# Dise_o_de_FISICA_v16.net
KiCad netlist of a schematic drawn in EAGLE
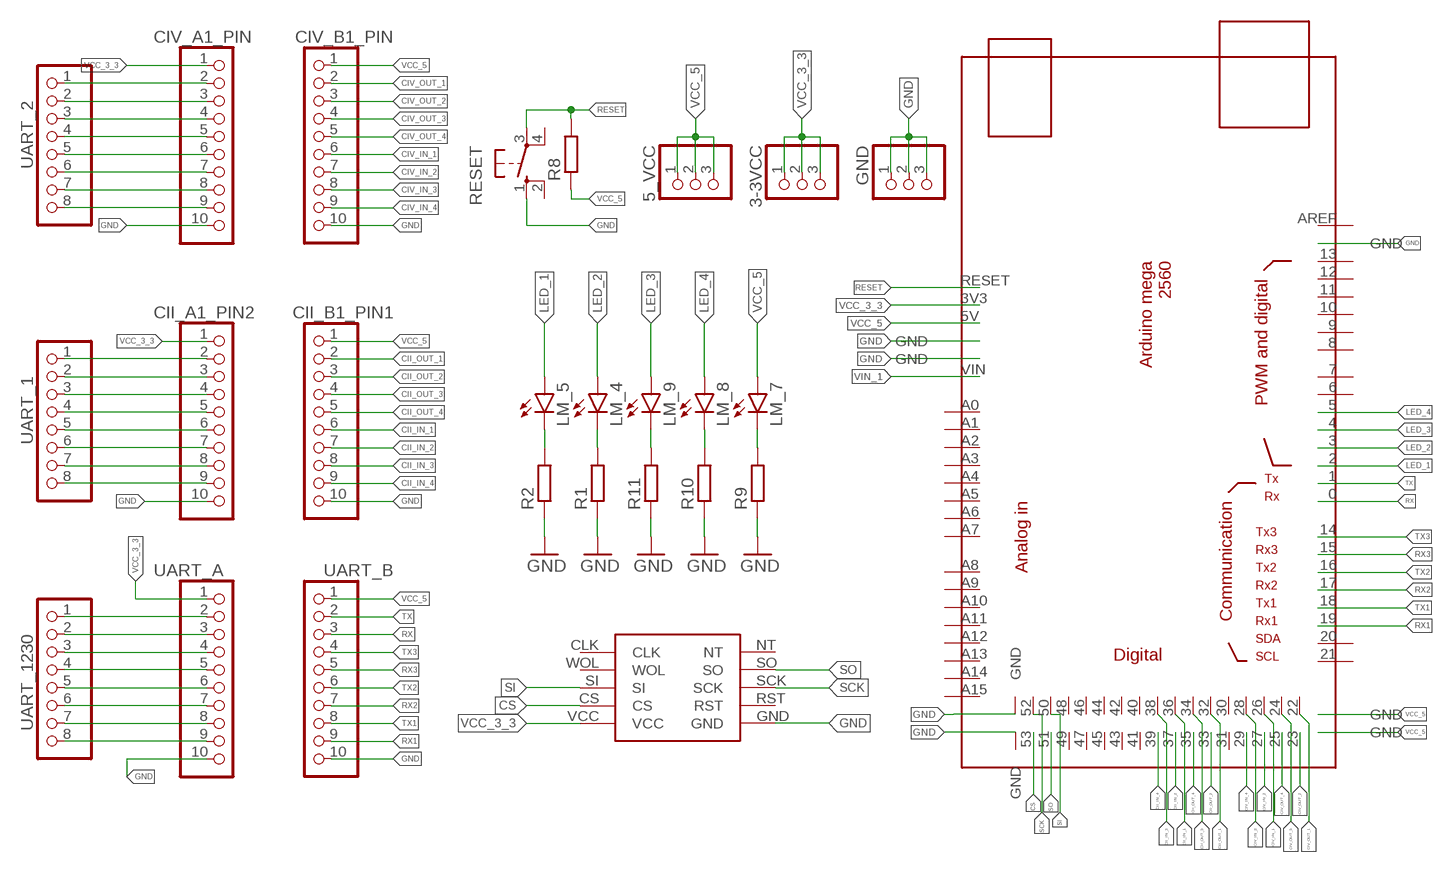
[diagram p0: schematic, sheet 1]

(export (version "E")
  (design (tool "Eeschema 10.0.6"))
  (components
    (comp (ref "3-3VCC")
      (value "PINHD-1X3")
      (footprint "eagle-import:1X03")
      (libsource (lib "eagle-import") (part "PINHD-1X3"))
    )
    (comp (ref "5_VCC")
      (value "PINHD-1X3")
      (footprint "eagle-import:1X03")
      (libsource (lib "eagle-import") (part "PINHD-1X3"))
    )
    (comp (ref "ARDUINOMEGA2560")
      (value "MEGA_DEVICE")
      (footprint "eagle-import:MEGAOUTLINE")
      (libsource (lib "eagle-import") (part "MEGA_DEVICE"))
    )
    (comp (ref "CII_A1_PIN2")
      (value "PINHD-1X10")
      (footprint "eagle-import:1X10-BIG")
      (libsource (lib "eagle-import") (part "PINHD-1X10"))
    )
    (comp (ref "CII_B1_PIN1")
      (value "PINHD-1X10")
      (footprint "eagle-import:1X10-BIG")
      (libsource (lib "eagle-import") (part "PINHD-1X10"))
    )
    (comp (ref "CIV_A1_PIN")
      (value "PINHD-1X10")
      (footprint "eagle-import:1X10-BIG")
      (libsource (lib "eagle-import") (part "PINHD-1X10"))
    )
    (comp (ref "CIV_B1_PIN")
      (value "PINHD-1X10")
      (footprint "eagle-import:1X10-BIG")
      (libsource (lib "eagle-import") (part "PINHD-1X10"))
    )
    (comp (ref "GND")
      (value "PINHD-1X3")
      (footprint "eagle-import:1X03")
      (libsource (lib "eagle-import") (part "PINHD-1X3"))
    )
    (comp (ref "LM_4")
      (value "LED3MM")
      (footprint "eagle-import:LED3MM")
      (libsource (lib "eagle-import") (part "LED3MM"))
    )
    (comp (ref "LM_5")
      (value "LED3MM")
      (footprint "eagle-import:LED3MM")
      (libsource (lib "eagle-import") (part "LED3MM"))
    )
    (comp (ref "LM_7")
      (value "LED3MM")
      (footprint "eagle-import:LED3MM")
      (libsource (lib "eagle-import") (part "LED3MM"))
    )
    (comp (ref "LM_8")
      (value "LED3MM")
      (footprint "eagle-import:LED3MM")
      (libsource (lib "eagle-import") (part "LED3MM"))
    )
    (comp (ref "LM_9")
      (value "LED3MM")
      (footprint "eagle-import:LED3MM")
      (libsource (lib "eagle-import") (part "LED3MM"))
    )
    (comp (ref "MODULO_ETHERNET")
      (value "ENC28J60")
      (footprint "eagle-import:ENC28J60")
      (libsource (lib "eagle-import") (part "ENC28J60"))
    )
    (comp (ref "R1")
      (value "R_CHIP-0805(2012-METRIC)")
      (footprint "eagle-import:RESC2012X65")
      (libsource (lib "eagle-import") (part "RCHIP-0805(2012-METRIC)_"))
    )
    (comp (ref "R2")
      (value "R_CHIP-0805(2012-METRIC)")
      (footprint "eagle-import:RESC2012X65")
      (libsource (lib "eagle-import") (part "RCHIP-0805(2012-METRIC)_"))
    )
    (comp (ref "R8")
      (value "R_CHIP-0805(2012-METRIC)")
      (footprint "eagle-import:RESC2012X65")
      (libsource (lib "eagle-import") (part "RCHIP-0805(2012-METRIC)_"))
    )
    (comp (ref "R9")
      (value "R_CHIP-0805(2012-METRIC)")
      (footprint "eagle-import:RESC2012X65")
      (libsource (lib "eagle-import") (part "RCHIP-0805(2012-METRIC)_"))
    )
    (comp (ref "R10")
      (value "R_CHIP-0805(2012-METRIC)")
      (footprint "eagle-import:RESC2012X65")
      (libsource (lib "eagle-import") (part "RCHIP-0805(2012-METRIC)_"))
    )
    (comp (ref "R11")
      (value "R_CHIP-0805(2012-METRIC)")
      (footprint "eagle-import:RESC2012X65")
      (libsource (lib "eagle-import") (part "RCHIP-0805(2012-METRIC)_"))
    )
    (comp (ref "RESET")
      (value "10-XX")
      (footprint "eagle-import:B3F-10XX")
      (fields (field (name "MPN") "B3F-1000"))
      (libsource (lib "eagle-import") (part "10-XX"))
    )
    (comp (ref "UART_1")
      (value "PINHD-1X8CLEANBIG")
      (footprint "eagle-import:1X08-CLEANBIG")
      (libsource (lib "eagle-import") (part "PINHD-1X8CLEANBIG"))
    )
    (comp (ref "UART_2")
      (value "PINHD-1X8CLEANBIG")
      (footprint "eagle-import:1X08-CLEANBIG")
      (libsource (lib "eagle-import") (part "PINHD-1X8CLEANBIG"))
    )
    (comp (ref "UART_1230")
      (value "PINHD-1X8CLEANBIG")
      (footprint "eagle-import:1X08-CLEANBIG")
      (libsource (lib "eagle-import") (part "PINHD-1X8CLEANBIG"))
    )
    (comp (ref "UART_A")
      (value "PINHD-1X10")
      (footprint "eagle-import:1X10-BIG")
      (libsource (lib "eagle-import") (part "PINHD-1X10"))
    )
    (comp (ref "UART_B")
      (value "PINHD-1X10")
      (footprint "eagle-import:1X10-BIG")
      (libsource (lib "eagle-import") (part "PINHD-1X10"))
    )
  )
  (nets
    (net (code "1") (name "CII_IN_1") (class "Default")
      (node (ref "ARDUINOMEGA2560") (pin "36") (pinfunction "36_36") (pintype "bidirectional"))
      (node (ref "CII_B1_PIN1") (pin "6") (pinfunction "6_6") (pintype "passive"))
    )
    (net (code "2") (name "CII_IN_2") (class "Default")
      (node (ref "ARDUINOMEGA2560") (pin "37") (pinfunction "37_37") (pintype "bidirectional"))
      (node (ref "CII_B1_PIN1") (pin "7") (pinfunction "7_7") (pintype "passive"))
    )
    (net (code "3") (name "CII_IN_3") (class "Default")
      (node (ref "ARDUINOMEGA2560") (pin "38") (pinfunction "38_38") (pintype "bidirectional"))
      (node (ref "CII_B1_PIN1") (pin "8") (pinfunction "8_8") (pintype "passive"))
    )
    (net (code "4") (name "CII_IN_4") (class "Default")
      (node (ref "ARDUINOMEGA2560") (pin "39") (pinfunction "39_39") (pintype "bidirectional"))
      (node (ref "CII_B1_PIN1") (pin "9") (pinfunction "9_9") (pintype "passive"))
    )
    (net (code "5") (name "CII_OUT_1") (class "Default")
      (node (ref "ARDUINOMEGA2560") (pin "32") (pinfunction "32_32") (pintype "bidirectional"))
      (node (ref "CII_B1_PIN1") (pin "2") (pinfunction "2_2") (pintype "passive"))
    )
    (net (code "6") (name "CII_OUT_2") (class "Default")
      (node (ref "ARDUINOMEGA2560") (pin "33") (pinfunction "33_33") (pintype "bidirectional"))
      (node (ref "CII_B1_PIN1") (pin "3") (pinfunction "3_3") (pintype "passive"))
    )
    (net (code "7") (name "CII_OUT_3") (class "Default")
      (node (ref "ARDUINOMEGA2560") (pin "34") (pinfunction "34_34") (pintype "bidirectional"))
      (node (ref "CII_B1_PIN1") (pin "4") (pinfunction "4_4") (pintype "passive"))
    )
    (net (code "8") (name "CII_OUT_4") (class "Default")
      (node (ref "ARDUINOMEGA2560") (pin "35") (pinfunction "35_35") (pintype "bidirectional"))
      (node (ref "CII_B1_PIN1") (pin "5") (pinfunction "5_5") (pintype "passive"))
    )
    (net (code "9") (name "CIV_IN_1") (class "Default")
      (node (ref "ARDUINOMEGA2560") (pin "26") (pinfunction "26_26") (pintype "bidirectional"))
      (node (ref "CIV_B1_PIN") (pin "6") (pinfunction "6_6") (pintype "passive"))
    )
    (net (code "10") (name "CIV_IN_2") (class "Default")
      (node (ref "ARDUINOMEGA2560") (pin "27") (pinfunction "27_27") (pintype "bidirectional"))
      (node (ref "CIV_B1_PIN") (pin "7") (pinfunction "7_7") (pintype "passive"))
    )
    (net (code "11") (name "CIV_IN_3") (class "Default")
      (node (ref "ARDUINOMEGA2560") (pin "28") (pinfunction "28_28") (pintype "bidirectional"))
      (node (ref "CIV_B1_PIN") (pin "8") (pinfunction "8_8") (pintype "passive"))
    )
    (net (code "12") (name "CIV_IN_4") (class "Default")
      (node (ref "ARDUINOMEGA2560") (pin "29") (pinfunction "29_29") (pintype "bidirectional"))
      (node (ref "CIV_B1_PIN") (pin "9") (pinfunction "9_9") (pintype "passive"))
    )
    (net (code "13") (name "CIV_OUT_1") (class "Default")
      (node (ref "ARDUINOMEGA2560") (pin "22") (pinfunction "22_22") (pintype "bidirectional"))
      (node (ref "CIV_B1_PIN") (pin "2") (pinfunction "2_2") (pintype "passive"))
    )
    (net (code "14") (name "CIV_OUT_2") (class "Default")
      (node (ref "ARDUINOMEGA2560") (pin "23") (pinfunction "23_23") (pintype "bidirectional"))
      (node (ref "CIV_B1_PIN") (pin "3") (pinfunction "3_3") (pintype "passive"))
    )
    (net (code "15") (name "CIV_OUT_3") (class "Default")
      (node (ref "ARDUINOMEGA2560") (pin "24") (pinfunction "24_24") (pintype "bidirectional"))
      (node (ref "CIV_B1_PIN") (pin "4") (pinfunction "4_4") (pintype "passive"))
    )
    (net (code "16") (name "CIV_OUT_4") (class "Default")
      (node (ref "ARDUINOMEGA2560") (pin "25") (pinfunction "25_25") (pintype "bidirectional"))
      (node (ref "CIV_B1_PIN") (pin "5") (pinfunction "5_5") (pintype "passive"))
    )
    (net (code "17") (name "CS") (class "Default")
      (node (ref "ARDUINOMEGA2560") (pin "53") (pinfunction "53_53") (pintype "bidirectional"))
      (node (ref "MODULO_ETHERNET") (pin "CS") (pinfunction "CS_CS") (pintype "bidirectional"))
    )
    (net (code "18") (name "GND") (class "Default")
      (node (ref "ARDUINOMEGA2560") (pin "GND@1") (pinfunction "GND_GND@1") (pintype "bidirectional"))
      (node (ref "ARDUINOMEGA2560") (pin "GND@2") (pinfunction "GND_GND@2") (pintype "bidirectional"))
      (node (ref "ARDUINOMEGA2560") (pin "GND@3") (pinfunction "GND_GND@3") (pintype "bidirectional"))
      (node (ref "ARDUINOMEGA2560") (pin "GND@6") (pinfunction "GND_GND@6") (pintype "bidirectional"))
      (node (ref "ARDUINOMEGA2560") (pin "GND@7") (pinfunction "GND_GND@7") (pintype "bidirectional"))
      (node (ref "CII_A1_PIN2") (pin "10") (pinfunction "10_10") (pintype "passive"))
      (node (ref "CII_B1_PIN1") (pin "10") (pinfunction "10_10") (pintype "passive"))
      (node (ref "CIV_A1_PIN") (pin "10") (pinfunction "10_10") (pintype "passive"))
      (node (ref "CIV_B1_PIN") (pin "10") (pinfunction "10_10") (pintype "passive"))
      (node (ref "GND") (pin "1") (pinfunction "1_1") (pintype "passive"))
      (node (ref "GND") (pin "2") (pinfunction "2_2") (pintype "passive"))
      (node (ref "GND") (pin "3") (pinfunction "3_3") (pintype "passive"))
      (node (ref "MODULO_ETHERNET") (pin "GND") (pinfunction "GND_GND") (pintype "bidirectional"))
      (node (ref "R1") (pin "1") (pinfunction "1_1") (pintype "passive"))
      (node (ref "R10") (pin "1") (pinfunction "1_1") (pintype "passive"))
      (node (ref "R11") (pin "1") (pinfunction "1_1") (pintype "passive"))
      (node (ref "R2") (pin "1") (pinfunction "1_1") (pintype "passive"))
      (node (ref "R9") (pin "1") (pinfunction "1_1") (pintype "passive"))
      (node (ref "RESET") (pin "1") (pinfunction "S_1") (pintype "passive"))
      (node (ref "UART_A") (pin "10") (pinfunction "10_10") (pintype "passive"))
      (node (ref "UART_B") (pin "10") (pinfunction "10_10") (pintype "passive"))
    )
    (net (code "19") (name "LED_1") (class "Default")
      (node (ref "ARDUINOMEGA2560") (pin "2") (pinfunction "2_2") (pintype "bidirectional"))
      (node (ref "LM_5") (pin "A") (pinfunction "A_A") (pintype "passive"))
    )
    (net (code "20") (name "LED_2") (class "Default")
      (node (ref "ARDUINOMEGA2560") (pin "3") (pinfunction "3_3") (pintype "bidirectional"))
      (node (ref "LM_4") (pin "A") (pinfunction "A_A") (pintype "passive"))
    )
    (net (code "21") (name "LED_3") (class "Default")
      (node (ref "ARDUINOMEGA2560") (pin "4") (pinfunction "4_4") (pintype "bidirectional"))
      (node (ref "LM_9") (pin "A") (pinfunction "A_A") (pintype "passive"))
    )
    (net (code "22") (name "LED_4") (class "Default")
      (node (ref "ARDUINOMEGA2560") (pin "5") (pinfunction "5_5") (pintype "bidirectional"))
      (node (ref "LM_8") (pin "A") (pinfunction "A_A") (pintype "passive"))
    )
    (net (code "23") (name "Net-(CII_A1_PIN2-Pad2)") (class "Default")
      (node (ref "CII_A1_PIN2") (pin "2") (pinfunction "2_2") (pintype "passive"))
      (node (ref "UART_1") (pin "1") (pinfunction "1_1") (pintype "passive"))
    )
    (net (code "24") (name "Net-(CII_A1_PIN2-Pad3)") (class "Default")
      (node (ref "CII_A1_PIN2") (pin "3") (pinfunction "3_3") (pintype "passive"))
      (node (ref "UART_1") (pin "2") (pinfunction "2_2") (pintype "passive"))
    )
    (net (code "25") (name "Net-(CII_A1_PIN2-Pad4)") (class "Default")
      (node (ref "CII_A1_PIN2") (pin "4") (pinfunction "4_4") (pintype "passive"))
      (node (ref "UART_1") (pin "3") (pinfunction "3_3") (pintype "passive"))
    )
    (net (code "26") (name "Net-(CII_A1_PIN2-Pad5)") (class "Default")
      (node (ref "CII_A1_PIN2") (pin "5") (pinfunction "5_5") (pintype "passive"))
      (node (ref "UART_1") (pin "4") (pinfunction "4_4") (pintype "passive"))
    )
    (net (code "27") (name "Net-(CII_A1_PIN2-Pad6)") (class "Default")
      (node (ref "CII_A1_PIN2") (pin "6") (pinfunction "6_6") (pintype "passive"))
      (node (ref "UART_1") (pin "5") (pinfunction "5_5") (pintype "passive"))
    )
    (net (code "28") (name "Net-(CII_A1_PIN2-Pad7)") (class "Default")
      (node (ref "CII_A1_PIN2") (pin "7") (pinfunction "7_7") (pintype "passive"))
      (node (ref "UART_1") (pin "6") (pinfunction "6_6") (pintype "passive"))
    )
    (net (code "29") (name "Net-(CII_A1_PIN2-Pad8)") (class "Default")
      (node (ref "CII_A1_PIN2") (pin "8") (pinfunction "8_8") (pintype "passive"))
      (node (ref "UART_1") (pin "7") (pinfunction "7_7") (pintype "passive"))
    )
    (net (code "30") (name "Net-(CII_A1_PIN2-Pad9)") (class "Default")
      (node (ref "CII_A1_PIN2") (pin "9") (pinfunction "9_9") (pintype "passive"))
      (node (ref "UART_1") (pin "8") (pinfunction "8_8") (pintype "passive"))
    )
    (net (code "31") (name "Net-(CIV_A1_PIN-Pad2)") (class "Default")
      (node (ref "CIV_A1_PIN") (pin "2") (pinfunction "2_2") (pintype "passive"))
      (node (ref "UART_2") (pin "1") (pinfunction "1_1") (pintype "passive"))
    )
    (net (code "32") (name "Net-(CIV_A1_PIN-Pad3)") (class "Default")
      (node (ref "CIV_A1_PIN") (pin "3") (pinfunction "3_3") (pintype "passive"))
      (node (ref "UART_2") (pin "2") (pinfunction "2_2") (pintype "passive"))
    )
    (net (code "33") (name "Net-(CIV_A1_PIN-Pad4)") (class "Default")
      (node (ref "CIV_A1_PIN") (pin "4") (pinfunction "4_4") (pintype "passive"))
      (node (ref "UART_2") (pin "3") (pinfunction "3_3") (pintype "passive"))
    )
    (net (code "34") (name "Net-(CIV_A1_PIN-Pad5)") (class "Default")
      (node (ref "CIV_A1_PIN") (pin "5") (pinfunction "5_5") (pintype "passive"))
      (node (ref "UART_2") (pin "4") (pinfunction "4_4") (pintype "passive"))
    )
    (net (code "35") (name "Net-(CIV_A1_PIN-Pad6)") (class "Default")
      (node (ref "CIV_A1_PIN") (pin "6") (pinfunction "6_6") (pintype "passive"))
      (node (ref "UART_2") (pin "5") (pinfunction "5_5") (pintype "passive"))
    )
    (net (code "36") (name "Net-(CIV_A1_PIN-Pad7)") (class "Default")
      (node (ref "CIV_A1_PIN") (pin "7") (pinfunction "7_7") (pintype "passive"))
      (node (ref "UART_2") (pin "6") (pinfunction "6_6") (pintype "passive"))
    )
    (net (code "37") (name "Net-(CIV_A1_PIN-Pad8)") (class "Default")
      (node (ref "CIV_A1_PIN") (pin "8") (pinfunction "8_8") (pintype "passive"))
      (node (ref "UART_2") (pin "7") (pinfunction "7_7") (pintype "passive"))
    )
    (net (code "38") (name "Net-(CIV_A1_PIN-Pad9)") (class "Default")
      (node (ref "CIV_A1_PIN") (pin "9") (pinfunction "9_9") (pintype "passive"))
      (node (ref "UART_2") (pin "8") (pinfunction "8_8") (pintype "passive"))
    )
    (net (code "39") (name "Net-(LM_4-C)") (class "Default")
      (node (ref "LM_4") (pin "K") (pinfunction "C_K") (pintype "passive"))
      (node (ref "R1") (pin "2") (pinfunction "2_2") (pintype "passive"))
    )
    (net (code "40") (name "Net-(LM_5-C)") (class "Default")
      (node (ref "LM_5") (pin "K") (pinfunction "C_K") (pintype "passive"))
      (node (ref "R2") (pin "2") (pinfunction "2_2") (pintype "passive"))
    )
    (net (code "41") (name "Net-(LM_7-C)") (class "Default")
      (node (ref "LM_7") (pin "K") (pinfunction "C_K") (pintype "passive"))
      (node (ref "R9") (pin "2") (pinfunction "2_2") (pintype "passive"))
    )
    (net (code "42") (name "Net-(LM_8-C)") (class "Default")
      (node (ref "LM_8") (pin "K") (pinfunction "C_K") (pintype "passive"))
      (node (ref "R10") (pin "2") (pinfunction "2_2") (pintype "passive"))
    )
    (net (code "43") (name "Net-(LM_9-C)") (class "Default")
      (node (ref "LM_9") (pin "K") (pinfunction "C_K") (pintype "passive"))
      (node (ref "R11") (pin "2") (pinfunction "2_2") (pintype "passive"))
    )
    (net (code "44") (name "Net-(UART_1230-Pad1)") (class "Default")
      (node (ref "UART_1230") (pin "1") (pinfunction "1_1") (pintype "passive"))
      (node (ref "UART_A") (pin "2") (pinfunction "2_2") (pintype "passive"))
    )
    (net (code "45") (name "Net-(UART_1230-Pad2)") (class "Default")
      (node (ref "UART_1230") (pin "2") (pinfunction "2_2") (pintype "passive"))
      (node (ref "UART_A") (pin "3") (pinfunction "3_3") (pintype "passive"))
    )
    (net (code "46") (name "Net-(UART_1230-Pad3)") (class "Default")
      (node (ref "UART_1230") (pin "3") (pinfunction "3_3") (pintype "passive"))
      (node (ref "UART_A") (pin "4") (pinfunction "4_4") (pintype "passive"))
    )
    (net (code "47") (name "Net-(UART_1230-Pad4)") (class "Default")
      (node (ref "UART_1230") (pin "4") (pinfunction "4_4") (pintype "passive"))
      (node (ref "UART_A") (pin "5") (pinfunction "5_5") (pintype "passive"))
    )
    (net (code "48") (name "Net-(UART_1230-Pad5)") (class "Default")
      (node (ref "UART_1230") (pin "5") (pinfunction "5_5") (pintype "passive"))
      (node (ref "UART_A") (pin "6") (pinfunction "6_6") (pintype "passive"))
    )
    (net (code "49") (name "Net-(UART_1230-Pad6)") (class "Default")
      (node (ref "UART_1230") (pin "6") (pinfunction "6_6") (pintype "passive"))
      (node (ref "UART_A") (pin "7") (pinfunction "7_7") (pintype "passive"))
    )
    (net (code "50") (name "Net-(UART_1230-Pad7)") (class "Default")
      (node (ref "UART_1230") (pin "7") (pinfunction "7_7") (pintype "passive"))
      (node (ref "UART_A") (pin "8") (pinfunction "8_8") (pintype "passive"))
    )
    (net (code "51") (name "Net-(UART_1230-Pad8)") (class "Default")
      (node (ref "UART_1230") (pin "8") (pinfunction "8_8") (pintype "passive"))
      (node (ref "UART_A") (pin "9") (pinfunction "9_9") (pintype "passive"))
    )
    (net (code "52") (name "RESET") (class "Default")
      (node (ref "ARDUINOMEGA2560") (pin "RESET") (pinfunction "RESET_RESET") (pintype "bidirectional"))
      (node (ref "R8") (pin "2") (pinfunction "2_2") (pintype "passive"))
      (node (ref "RESET") (pin "3") (pinfunction "P_3") (pintype "passive"))
    )
    (net (code "53") (name "RX") (class "Default")
      (node (ref "ARDUINOMEGA2560") (pin "0") (pinfunction "0_0") (pintype "bidirectional"))
      (node (ref "UART_B") (pin "3") (pinfunction "3_3") (pintype "passive"))
    )
    (net (code "54") (name "RX1") (class "Default")
      (node (ref "ARDUINOMEGA2560") (pin "19") (pinfunction "19_19") (pintype "bidirectional"))
      (node (ref "UART_B") (pin "9") (pinfunction "9_9") (pintype "passive"))
    )
    (net (code "55") (name "RX2") (class "Default")
      (node (ref "ARDUINOMEGA2560") (pin "17") (pinfunction "17_17") (pintype "bidirectional"))
      (node (ref "UART_B") (pin "7") (pinfunction "7_7") (pintype "passive"))
    )
    (net (code "56") (name "RX3") (class "Default")
      (node (ref "ARDUINOMEGA2560") (pin "15") (pinfunction "15_15") (pintype "bidirectional"))
      (node (ref "UART_B") (pin "5") (pinfunction "5_5") (pintype "passive"))
    )
    (net (code "57") (name "SCK") (class "Default")
      (node (ref "ARDUINOMEGA2560") (pin "52") (pinfunction "52_52") (pintype "bidirectional"))
      (node (ref "MODULO_ETHERNET") (pin "SCK") (pinfunction "SCK_SCK") (pintype "bidirectional"))
    )
    (net (code "58") (name "SI") (class "Default")
      (node (ref "ARDUINOMEGA2560") (pin "50") (pinfunction "50_50") (pintype "bidirectional"))
      (node (ref "MODULO_ETHERNET") (pin "SI") (pinfunction "SI_SI") (pintype "bidirectional"))
    )
    (net (code "59") (name "SO") (class "Default")
      (node (ref "ARDUINOMEGA2560") (pin "51") (pinfunction "51_51") (pintype "bidirectional"))
      (node (ref "MODULO_ETHERNET") (pin "SO") (pinfunction "SO_SO") (pintype "bidirectional"))
    )
    (net (code "60") (name "TX") (class "Default")
      (node (ref "ARDUINOMEGA2560") (pin "1") (pinfunction "1_1") (pintype "bidirectional"))
      (node (ref "UART_B") (pin "2") (pinfunction "2_2") (pintype "passive"))
    )
    (net (code "61") (name "TX1") (class "Default")
      (node (ref "ARDUINOMEGA2560") (pin "18") (pinfunction "18_18") (pintype "bidirectional"))
      (node (ref "UART_B") (pin "8") (pinfunction "8_8") (pintype "passive"))
    )
    (net (code "62") (name "TX2") (class "Default")
      (node (ref "ARDUINOMEGA2560") (pin "16") (pinfunction "16_16") (pintype "bidirectional"))
      (node (ref "UART_B") (pin "6") (pinfunction "6_6") (pintype "passive"))
    )
    (net (code "63") (name "TX3") (class "Default")
      (node (ref "ARDUINOMEGA2560") (pin "14") (pinfunction "14_14") (pintype "bidirectional"))
      (node (ref "UART_B") (pin "4") (pinfunction "4_4") (pintype "passive"))
    )
    (net (code "64") (name "VCC_3_3") (class "Default")
      (node (ref "3-3VCC") (pin "1") (pinfunction "1_1") (pintype "passive"))
      (node (ref "3-3VCC") (pin "2") (pinfunction "2_2") (pintype "passive"))
      (node (ref "3-3VCC") (pin "3") (pinfunction "3_3") (pintype "passive"))
      (node (ref "ARDUINOMEGA2560") (pin "3V3") (pinfunction "3V3_3V3") (pintype "bidirectional"))
      (node (ref "CII_A1_PIN2") (pin "1") (pinfunction "1_1") (pintype "passive"))
      (node (ref "CIV_A1_PIN") (pin "1") (pinfunction "1_1") (pintype "passive"))
      (node (ref "MODULO_ETHERNET") (pin "VCC") (pinfunction "VCC_VCC") (pintype "bidirectional"))
      (node (ref "UART_A") (pin "1") (pinfunction "1_1") (pintype "passive"))
    )
    (net (code "65") (name "VCC_5") (class "Default")
      (node (ref "5_VCC") (pin "1") (pinfunction "1_1") (pintype "passive"))
      (node (ref "5_VCC") (pin "2") (pinfunction "2_2") (pintype "passive"))
      (node (ref "5_VCC") (pin "3") (pinfunction "3_3") (pintype "passive"))
      (node (ref "ARDUINOMEGA2560") (pin "5V") (pinfunction "5V_5V") (pintype "bidirectional"))
      (node (ref "ARDUINOMEGA2560") (pin "GND@4") (pinfunction "GND_GND@4") (pintype "bidirectional"))
      (node (ref "ARDUINOMEGA2560") (pin "GND@5") (pinfunction "GND_GND@5") (pintype "bidirectional"))
      (node (ref "CII_B1_PIN1") (pin "1") (pinfunction "1_1") (pintype "passive"))
      (node (ref "CIV_B1_PIN") (pin "1") (pinfunction "1_1") (pintype "passive"))
      (node (ref "LM_7") (pin "A") (pinfunction "A_A") (pintype "passive"))
      (node (ref "R8") (pin "1") (pinfunction "1_1") (pintype "passive"))
      (node (ref "UART_B") (pin "1") (pinfunction "1_1") (pintype "passive"))
    )
    (net (code "66") (name "VIN_1") (class "Default")
      (node (ref "ARDUINOMEGA2560") (pin "VIN") (pinfunction "VIN_VIN") (pintype "bidirectional"))
    )
    (net (code "67") (name "unconnected-(ARDUINOMEGA2560-Pad6)") (class "Default")
      (node (ref "ARDUINOMEGA2560") (pin "6") (pinfunction "6_6") (pintype "bidirectional"))
    )
    (net (code "68") (name "unconnected-(ARDUINOMEGA2560-Pad7)") (class "Default")
      (node (ref "ARDUINOMEGA2560") (pin "7") (pinfunction "7_7") (pintype "bidirectional"))
    )
    (net (code "69") (name "unconnected-(ARDUINOMEGA2560-Pad8)") (class "Default")
      (node (ref "ARDUINOMEGA2560") (pin "8") (pinfunction "8_8") (pintype "bidirectional"))
    )
    (net (code "70") (name "unconnected-(ARDUINOMEGA2560-Pad9)") (class "Default")
      (node (ref "ARDUINOMEGA2560") (pin "9") (pinfunction "9_9") (pintype "bidirectional"))
    )
    (net (code "71") (name "unconnected-(ARDUINOMEGA2560-Pad10)") (class "Default")
      (node (ref "ARDUINOMEGA2560") (pin "10") (pinfunction "10_10") (pintype "bidirectional"))
    )
    (net (code "72") (name "unconnected-(ARDUINOMEGA2560-Pad11)") (class "Default")
      (node (ref "ARDUINOMEGA2560") (pin "11") (pinfunction "11_11") (pintype "bidirectional"))
    )
    (net (code "73") (name "unconnected-(ARDUINOMEGA2560-Pad12)") (class "Default")
      (node (ref "ARDUINOMEGA2560") (pin "12") (pinfunction "12_12") (pintype "bidirectional"))
    )
    (net (code "74") (name "unconnected-(ARDUINOMEGA2560-Pad13)") (class "Default")
      (node (ref "ARDUINOMEGA2560") (pin "13") (pinfunction "13_13") (pintype "bidirectional"))
    )
    (net (code "75") (name "unconnected-(ARDUINOMEGA2560-Pad20)") (class "Default")
      (node (ref "ARDUINOMEGA2560") (pin "20") (pinfunction "20_20") (pintype "bidirectional"))
    )
    (net (code "76") (name "unconnected-(ARDUINOMEGA2560-Pad21)") (class "Default")
      (node (ref "ARDUINOMEGA2560") (pin "21") (pinfunction "21_21") (pintype "bidirectional"))
    )
    (net (code "77") (name "unconnected-(ARDUINOMEGA2560-Pad30)") (class "Default")
      (node (ref "ARDUINOMEGA2560") (pin "30") (pinfunction "30_30") (pintype "bidirectional"))
    )
    (net (code "78") (name "unconnected-(ARDUINOMEGA2560-Pad31)") (class "Default")
      (node (ref "ARDUINOMEGA2560") (pin "31") (pinfunction "31_31") (pintype "bidirectional"))
    )
    (net (code "79") (name "unconnected-(ARDUINOMEGA2560-Pad40)") (class "Default")
      (node (ref "ARDUINOMEGA2560") (pin "40") (pinfunction "40_40") (pintype "bidirectional"))
    )
    (net (code "80") (name "unconnected-(ARDUINOMEGA2560-Pad41)") (class "Default")
      (node (ref "ARDUINOMEGA2560") (pin "41") (pinfunction "41_41") (pintype "bidirectional"))
    )
    (net (code "81") (name "unconnected-(ARDUINOMEGA2560-Pad42)") (class "Default")
      (node (ref "ARDUINOMEGA2560") (pin "42") (pinfunction "42_42") (pintype "bidirectional"))
    )
    (net (code "82") (name "unconnected-(ARDUINOMEGA2560-Pad43)") (class "Default")
      (node (ref "ARDUINOMEGA2560") (pin "43") (pinfunction "43_43") (pintype "bidirectional"))
    )
    (net (code "83") (name "unconnected-(ARDUINOMEGA2560-Pad44)") (class "Default")
      (node (ref "ARDUINOMEGA2560") (pin "44") (pinfunction "44_44") (pintype "bidirectional"))
    )
    (net (code "84") (name "unconnected-(ARDUINOMEGA2560-Pad45)") (class "Default")
      (node (ref "ARDUINOMEGA2560") (pin "45") (pinfunction "45_45") (pintype "bidirectional"))
    )
    (net (code "85") (name "unconnected-(ARDUINOMEGA2560-Pad46)") (class "Default")
      (node (ref "ARDUINOMEGA2560") (pin "46") (pinfunction "46_46") (pintype "bidirectional"))
    )
    (net (code "86") (name "unconnected-(ARDUINOMEGA2560-Pad47)") (class "Default")
      (node (ref "ARDUINOMEGA2560") (pin "47") (pinfunction "47_47") (pintype "bidirectional"))
    )
    (net (code "87") (name "unconnected-(ARDUINOMEGA2560-Pad48)") (class "Default")
      (node (ref "ARDUINOMEGA2560") (pin "48") (pinfunction "48_48") (pintype "bidirectional"))
    )
    (net (code "88") (name "unconnected-(ARDUINOMEGA2560-Pad49)") (class "Default")
      (node (ref "ARDUINOMEGA2560") (pin "49") (pinfunction "49_49") (pintype "bidirectional"))
    )
    (net (code "89") (name "unconnected-(ARDUINOMEGA2560-PadA0)") (class "Default")
      (node (ref "ARDUINOMEGA2560") (pin "A0") (pinfunction "A0_A0") (pintype "bidirectional"))
    )
    (net (code "90") (name "unconnected-(ARDUINOMEGA2560-PadA1)") (class "Default")
      (node (ref "ARDUINOMEGA2560") (pin "A1") (pinfunction "A1_A1") (pintype "bidirectional"))
    )
    (net (code "91") (name "unconnected-(ARDUINOMEGA2560-PadA2)") (class "Default")
      (node (ref "ARDUINOMEGA2560") (pin "A2") (pinfunction "A2_A2") (pintype "bidirectional"))
    )
    (net (code "92") (name "unconnected-(ARDUINOMEGA2560-PadA3)") (class "Default")
      (node (ref "ARDUINOMEGA2560") (pin "A3") (pinfunction "A3_A3") (pintype "bidirectional"))
    )
    (net (code "93") (name "unconnected-(ARDUINOMEGA2560-PadA4)") (class "Default")
      (node (ref "ARDUINOMEGA2560") (pin "A4") (pinfunction "A4_A4") (pintype "bidirectional"))
    )
    (net (code "94") (name "unconnected-(ARDUINOMEGA2560-PadA5)") (class "Default")
      (node (ref "ARDUINOMEGA2560") (pin "A5") (pinfunction "A5_A5") (pintype "bidirectional"))
    )
    (net (code "95") (name "unconnected-(ARDUINOMEGA2560-PadA6)") (class "Default")
      (node (ref "ARDUINOMEGA2560") (pin "A6") (pinfunction "A6_A6") (pintype "bidirectional"))
    )
    (net (code "96") (name "unconnected-(ARDUINOMEGA2560-PadA7)") (class "Default")
      (node (ref "ARDUINOMEGA2560") (pin "A7") (pinfunction "A7_A7") (pintype "bidirectional"))
    )
    (net (code "97") (name "unconnected-(ARDUINOMEGA2560-PadA8)") (class "Default")
      (node (ref "ARDUINOMEGA2560") (pin "A8") (pinfunction "A8_A8") (pintype "bidirectional"))
    )
    (net (code "98") (name "unconnected-(ARDUINOMEGA2560-PadA9)") (class "Default")
      (node (ref "ARDUINOMEGA2560") (pin "A9") (pinfunction "A9_A9") (pintype "bidirectional"))
    )
    (net (code "99") (name "unconnected-(ARDUINOMEGA2560-PadA10)") (class "Default")
      (node (ref "ARDUINOMEGA2560") (pin "A10") (pinfunction "A10_A10") (pintype "bidirectional"))
    )
    (net (code "100") (name "unconnected-(ARDUINOMEGA2560-PadA11)") (class "Default")
      (node (ref "ARDUINOMEGA2560") (pin "A11") (pinfunction "A11_A11") (pintype "bidirectional"))
    )
    (net (code "101") (name "unconnected-(ARDUINOMEGA2560-PadA12)") (class "Default")
      (node (ref "ARDUINOMEGA2560") (pin "A12") (pinfunction "A12_A12") (pintype "bidirectional"))
    )
    (net (code "102") (name "unconnected-(ARDUINOMEGA2560-PadA13)") (class "Default")
      (node (ref "ARDUINOMEGA2560") (pin "A13") (pinfunction "A13_A13") (pintype "bidirectional"))
    )
    (net (code "103") (name "unconnected-(ARDUINOMEGA2560-PadA14)") (class "Default")
      (node (ref "ARDUINOMEGA2560") (pin "A14") (pinfunction "A14_A14") (pintype "bidirectional"))
    )
    (net (code "104") (name "unconnected-(ARDUINOMEGA2560-PadA15)") (class "Default")
      (node (ref "ARDUINOMEGA2560") (pin "A15") (pinfunction "A15_A15") (pintype "bidirectional"))
    )
    (net (code "105") (name "unconnected-(ARDUINOMEGA2560-PadAREF)") (class "Default")
      (node (ref "ARDUINOMEGA2560") (pin "AREF") (pinfunction "AREF_AREF") (pintype "bidirectional"))
    )
    (net (code "106") (name "unconnected-(MODULO_ETHERNET-PadCLK)") (class "Default")
      (node (ref "MODULO_ETHERNET") (pin "CLK") (pinfunction "CLK_CLK") (pintype "bidirectional"))
    )
    (net (code "107") (name "unconnected-(MODULO_ETHERNET-PadNT)") (class "Default")
      (node (ref "MODULO_ETHERNET") (pin "NT") (pinfunction "NT_NT") (pintype "bidirectional"))
    )
    (net (code "108") (name "unconnected-(MODULO_ETHERNET-PadRST)") (class "Default")
      (node (ref "MODULO_ETHERNET") (pin "RST") (pinfunction "RST_RST") (pintype "bidirectional"))
    )
    (net (code "109") (name "unconnected-(MODULO_ETHERNET-PadWOL)") (class "Default")
      (node (ref "MODULO_ETHERNET") (pin "WOL") (pinfunction "WOL_WOL") (pintype "bidirectional"))
    )
    (net (code "110") (name "unconnected-(RESET-P1-Pad4)") (class "Default")
      (node (ref "RESET") (pin "4") (pinfunction "P1_4") (pintype "passive"))
    )
    (net (code "111") (name "unconnected-(RESET-S1-Pad2)") (class "Default")
      (node (ref "RESET") (pin "2") (pinfunction "S1_2") (pintype "passive"))
    )
  )
)
